# CPU_STM32F4.net
KiCad netlist of a schematic drawn in Altium Designer
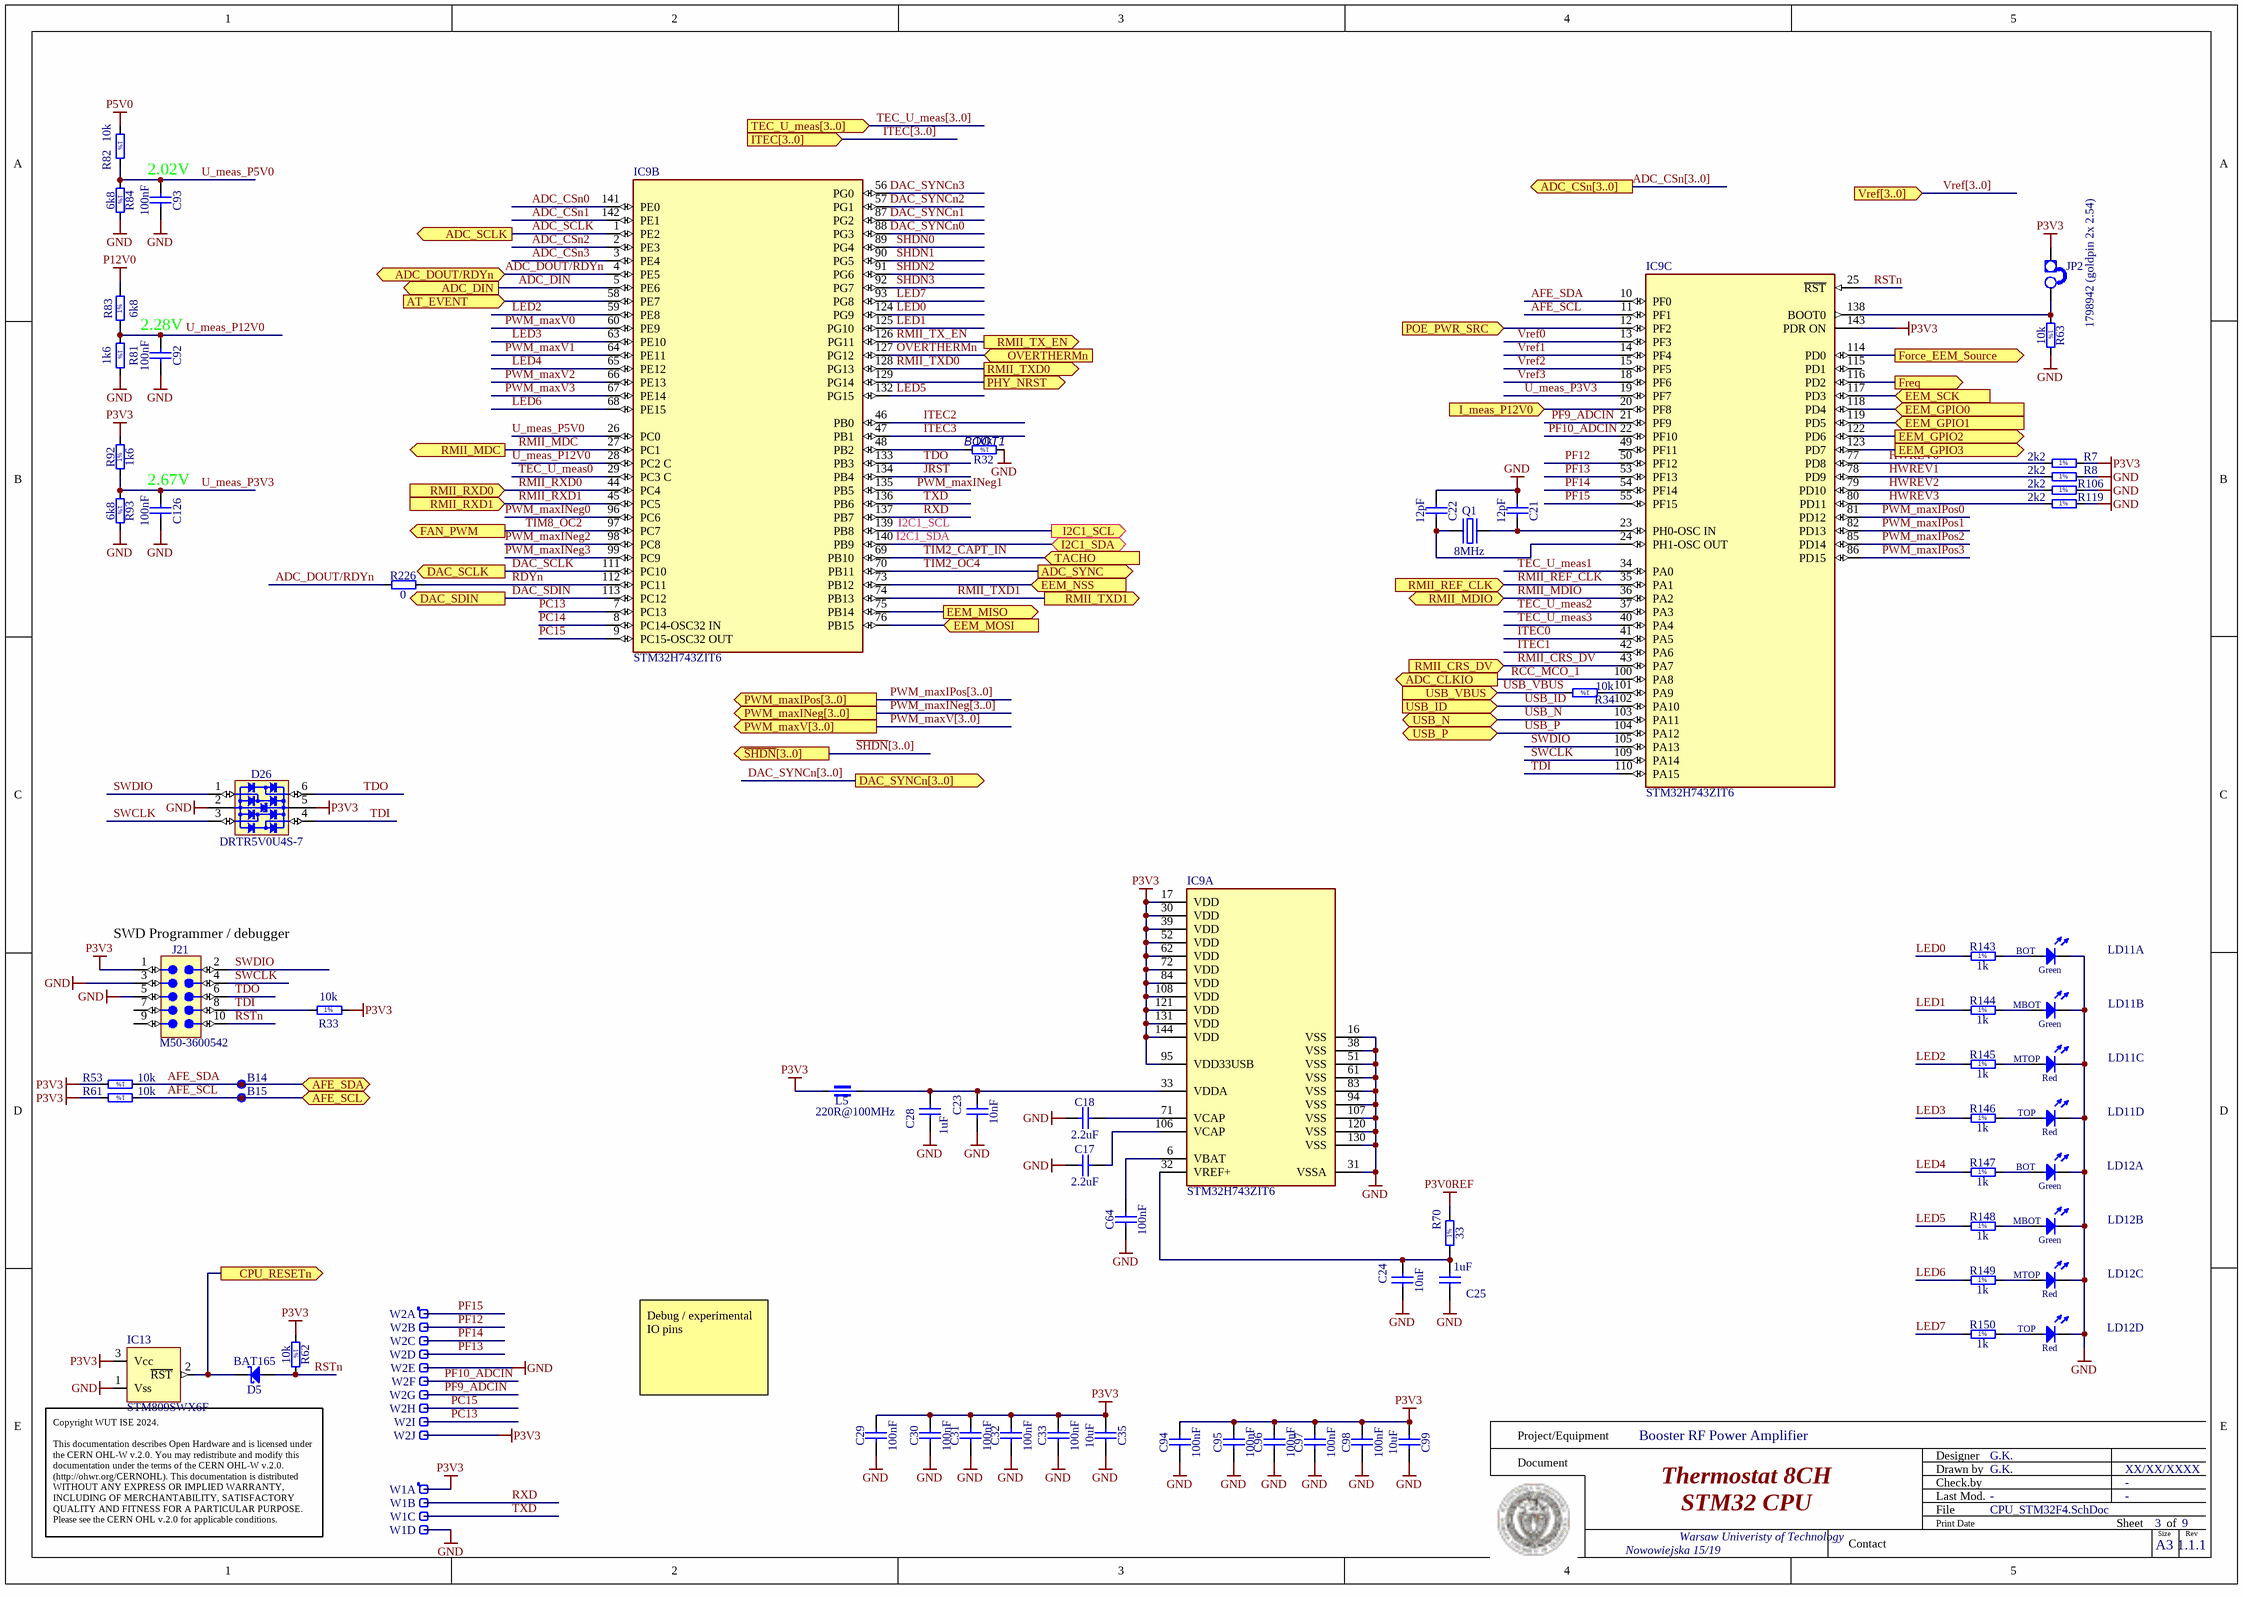
[diagram p0: CPU_STM32F4.SchDoc]

(export (version "E")
  (design (tool "Eeschema 10.0.6"))
  (components
    (comp (ref "B14")
      (value "SMD Pad")
      (footprint "C100")
      (description "Through Hole Pad")
      (fields (field (name "PART NUMBER") "SMD_PAD_D1MM") (field (name "AUTHOR") "CERN DEM JLC"))
      (libsource (lib "Eletro-mechanical") (part "Single SMD Pad (Round)"))
    )
    (comp (ref "B15")
      (value "SMD Pad")
      (footprint "C100")
      (description "Through Hole Pad")
      (fields (field (name "PART NUMBER") "SMD_PAD_D1MM") (field (name "AUTHOR") "CERN DEM JLC"))
      (libsource (lib "Eletro-mechanical") (part "Single SMD Pad (Round)"))
    )
    (comp (ref "C17")
      (value "2.2uF")
      (footprint "CAPC1608X90N")
      (description "Non-polarised capacitor")
      (fields
        (field (name "PART NUMBER") "CC0603_2.2UF_10V_20%_X7R")
        (field (name "VOLTAGE") "10V")
        (field (name "AUTHOR") "CERN DEM JLC")
      )
      (libsource (lib "Capacitors") (part "Capacitor - non polarized"))
    )
    (comp (ref "C18")
      (value "2.2uF")
      (footprint "CAPC1608X90N")
      (description "Non-polarised capacitor")
      (fields
        (field (name "PART NUMBER") "CC0603_2.2UF_10V_20%_X7R")
        (field (name "VOLTAGE") "10V")
        (field (name "AUTHOR") "CERN DEM JLC")
      )
      (libsource (lib "Capacitors") (part "Capacitor - non polarized"))
    )
    (comp (ref "C21")
      (value "12pF")
      (footprint "CAPC1005X55N")
      (description "Non-polarised capacitor")
      (fields
        (field (name "PART NUMBER") "CC0402_12PF_50V_5%_C0G")
        (field (name "VOLTAGE") "50V")
        (field (name "AUTHOR") "CERN DEM JLC")
      )
      (libsource (lib "Capacitors") (part "Capacitor - non polarized"))
    )
    (comp (ref "C22")
      (value "12pF")
      (footprint "CAPC1005X55N")
      (description "Non-polarised capacitor")
      (fields
        (field (name "PART NUMBER") "CC0402_12PF_50V_5%_C0G")
        (field (name "VOLTAGE") "50V")
        (field (name "AUTHOR") "CERN DEM JLC")
      )
      (libsource (lib "Capacitors") (part "Capacitor - non polarized"))
    )
    (comp (ref "C23")
      (value "10nF")
      (footprint "CAPC1005X55N")
      (description "Non-polarised capacitor")
      (fields
        (field (name "PART NUMBER") "CC0402_10NF_25V_10%_X7R")
        (field (name "VOLTAGE") "25V")
        (field (name "AUTHOR") "CERN DEM JLC")
      )
      (libsource (lib "Capacitors") (part "Capacitor - non polarized"))
    )
    (comp (ref "C24")
      (value "10nF")
      (footprint "CAPC1005X55N")
      (description "Non-polarised capacitor")
      (fields
        (field (name "PART NUMBER") "CC0402_10NF_25V_10%_X7R")
        (field (name "VOLTAGE") "25V")
        (field (name "AUTHOR") "CERN DEM JLC")
      )
      (libsource (lib "Capacitors") (part "Capacitor - non polarized"))
    )
    (comp (ref "C25")
      (value "1uF")
      (footprint "CAPC1608X87N")
      (description "Non-polarised capacitor")
      (fields
        (field (name "PART NUMBER") "CC0603_1UF_25V_10%_X7R")
        (field (name "VOLTAGE") "25V")
        (field (name "AUTHOR") "CERN DEM JLC")
      )
      (libsource (lib "Capacitors") (part "Capacitor - non polarized"))
    )
    (comp (ref "C28")
      (value "1uF")
      (footprint "CAPC1608X87N")
      (description "Non-polarised capacitor")
      (fields
        (field (name "PART NUMBER") "CC0603_1UF_25V_10%_X7R")
        (field (name "VOLTAGE") "25V")
        (field (name "AUTHOR") "CERN DEM JLC")
      )
      (libsource (lib "Capacitors") (part "Capacitor - non polarized"))
    )
    (comp (ref "C29")
      (value "100nF")
      (footprint "CAPC1005X55N")
      (description "Non-polarised capacitor")
      (fields
        (field (name "PART NUMBER") "CC0402_100NF_16V_10%_X5R")
        (field (name "VOLTAGE") "16V")
        (field (name "AUTHOR") "CERN DEM JLC")
      )
      (libsource (lib "Capacitors") (part "Capacitor - non polarized"))
    )
    (comp (ref "C30")
      (value "100nF")
      (footprint "CAPC1005X55N")
      (description "Non-polarised capacitor")
      (fields
        (field (name "PART NUMBER") "CC0402_100NF_16V_10%_X5R")
        (field (name "VOLTAGE") "16V")
        (field (name "AUTHOR") "CERN DEM JLC")
      )
      (libsource (lib "Capacitors") (part "Capacitor - non polarized"))
    )
    (comp (ref "C31")
      (value "100nF")
      (footprint "CAPC1005X55N")
      (description "Non-polarised capacitor")
      (fields
        (field (name "PART NUMBER") "CC0402_100NF_16V_10%_X5R")
        (field (name "VOLTAGE") "16V")
        (field (name "AUTHOR") "CERN DEM JLC")
      )
      (libsource (lib "Capacitors") (part "Capacitor - non polarized"))
    )
    (comp (ref "C32")
      (value "100nF")
      (footprint "CAPC1005X55N")
      (description "Non-polarised capacitor")
      (fields
        (field (name "PART NUMBER") "CC0402_100NF_16V_10%_X5R")
        (field (name "VOLTAGE") "16V")
        (field (name "AUTHOR") "CERN DEM JLC")
      )
      (libsource (lib "Capacitors") (part "Capacitor - non polarized"))
    )
    (comp (ref "C33")
      (value "100nF")
      (footprint "CAPC1005X55N")
      (description "Non-polarised capacitor")
      (fields
        (field (name "PART NUMBER") "CC0402_100NF_16V_10%_X5R")
        (field (name "VOLTAGE") "16V")
        (field (name "AUTHOR") "CERN DEM JLC")
      )
      (libsource (lib "Capacitors") (part "Capacitor - non polarized"))
    )
    (comp (ref "C35")
      (value "10uF")
      (footprint "CAPC2012X135N")
      (description "Non-polarised capacitor")
      (fields
        (field (name "PART NUMBER") "CC0805_10UF_16V_10%_X5R")
        (field (name "VOLTAGE") "16V")
        (field (name "AUTHOR") "CERN DEM JLC")
      )
      (libsource (lib "Capacitors") (part "Capacitor - non polarized"))
    )
    (comp (ref "C64")
      (value "100nF")
      (footprint "CAPC1005X55N")
      (description "Non-polarised capacitor")
      (fields
        (field (name "PART NUMBER") "CC0402_100NF_16V_10%_X5R")
        (field (name "VOLTAGE") "16V")
        (field (name "AUTHOR") "CERN DEM JLC")
      )
      (libsource (lib "Capacitors") (part "Capacitor - non polarized"))
    )
    (comp (ref "C92")
      (value "100nF")
      (footprint "CAPC1005X55N")
      (description "Non-polarised capacitor")
      (fields
        (field (name "PART NUMBER") "CC0402_100NF_16V_10%_X5R")
        (field (name "VOLTAGE") "16V")
        (field (name "AUTHOR") "CERN DEM JLC")
      )
      (libsource (lib "Capacitors") (part "Capacitor - non polarized"))
    )
    (comp (ref "C93")
      (value "100nF")
      (footprint "CAPC1005X55N")
      (description "Non-polarised capacitor")
      (fields
        (field (name "PART NUMBER") "CC0402_100NF_16V_10%_X5R")
        (field (name "VOLTAGE") "16V")
        (field (name "AUTHOR") "CERN DEM JLC")
      )
      (libsource (lib "Capacitors") (part "Capacitor - non polarized"))
    )
    (comp (ref "C94")
      (value "100nF")
      (footprint "CAPC1005X55N")
      (description "Non-polarised capacitor")
      (fields
        (field (name "PART NUMBER") "CC0402_100NF_16V_10%_X5R")
        (field (name "VOLTAGE") "16V")
        (field (name "AUTHOR") "CERN DEM JLC")
      )
      (libsource (lib "Capacitors") (part "Capacitor - non polarized"))
    )
    (comp (ref "C95")
      (value "100nF")
      (footprint "CAPC1005X55N")
      (description "Non-polarised capacitor")
      (fields
        (field (name "PART NUMBER") "CC0402_100NF_16V_10%_X5R")
        (field (name "VOLTAGE") "16V")
        (field (name "AUTHOR") "CERN DEM JLC")
      )
      (libsource (lib "Capacitors") (part "Capacitor - non polarized"))
    )
    (comp (ref "C96")
      (value "100nF")
      (footprint "CAPC1005X55N")
      (description "Non-polarised capacitor")
      (fields
        (field (name "PART NUMBER") "CC0402_100NF_16V_10%_X5R")
        (field (name "VOLTAGE") "16V")
        (field (name "AUTHOR") "CERN DEM JLC")
      )
      (libsource (lib "Capacitors") (part "Capacitor - non polarized"))
    )
    (comp (ref "C97")
      (value "100nF")
      (footprint "CAPC1005X55N")
      (description "Non-polarised capacitor")
      (fields
        (field (name "PART NUMBER") "CC0402_100NF_16V_10%_X5R")
        (field (name "VOLTAGE") "16V")
        (field (name "AUTHOR") "CERN DEM JLC")
      )
      (libsource (lib "Capacitors") (part "Capacitor - non polarized"))
    )
    (comp (ref "C98")
      (value "100nF")
      (footprint "CAPC1005X55N")
      (description "Non-polarised capacitor")
      (fields
        (field (name "PART NUMBER") "CC0402_100NF_16V_10%_X5R")
        (field (name "VOLTAGE") "16V")
        (field (name "AUTHOR") "CERN DEM JLC")
      )
      (libsource (lib "Capacitors") (part "Capacitor - non polarized"))
    )
    (comp (ref "C99")
      (value "10uF")
      (footprint "CAPC2012X135N")
      (description "Non-polarised capacitor")
      (fields
        (field (name "PART NUMBER") "CC0805_10UF_16V_10%_X5R")
        (field (name "VOLTAGE") "16V")
        (field (name "AUTHOR") "CERN DEM JLC")
      )
      (libsource (lib "Capacitors") (part "Capacitor - non polarized"))
    )
    (comp (ref "C126")
      (value "100nF")
      (footprint "CAPC1005X55N")
      (description "Non-polarised capacitor")
      (fields
        (field (name "PART NUMBER") "CC0402_100NF_16V_10%_X5R")
        (field (name "VOLTAGE") "16V")
        (field (name "AUTHOR") "CERN DEM JLC")
      )
      (libsource (lib "Capacitors") (part "Capacitor - non polarized"))
    )
    (comp (ref "D5")
      (value "BAT165")
      (footprint "SOD2512X110N")
      (description "Schottky Diode")
      (fields
        (field (name "VOLTAGE") "40V")
        (field (name "POWER") "750mA")
        (field (name "AUTHOR") "CERN DEM JLC")
      )
      (libsource (lib "ICs And Semiconductors") (part "Diode Schottky"))
    )
    (comp (ref "D26")
      (value "DRTR5V0U4S-7")
      (footprint "SOT65P210X110-6N")
      (description "Integrated Quad Ultra-Low Capacitance ESD Protection")
      (fields (field (name "MANUFACTURER") "DIODES") (field (name "AUTHOR") "GK"))
      (libsource (lib "Diodes") (part "D_TVS_DRTR5V0U4S-7"))
    )
    (comp (ref "IC9")
      (value "STM32H743ZIT6")
      (footprint "FP-LQFP144-1A-MFG")
      (description "IC MCU 32BIT 2MB FLASH 144LQFP")
      (fields
        (field (name "MANUFACTURER") "STMicroelectronics")
        (field (name "OCTOPART") "https://octopart.com/stm32h743zit6-stmicroelectronics-76372529")
      )
      (libsource (lib "Altium Content Vault") (part "4977c5c7f8d170b58ef15f889e64ba1"))
    )
    (comp (ref "IC13")
      (value "STM809SWX6F")
      (footprint "SOT-23")
      (description "2.93V  Reset circuit")
      (libsource (lib "LIBRARY_SCH") (part "VMON_STM809"))
    )
    (comp (ref "J21")
      (value "Header 10")
      (footprint "HARWIN_M50-3600542")
      (description "10 Contacts - Pitch 1.27mm - Dual Row SMT Vertical Pin Header (Post Lead = 3mm, Insulator 1mm)")
      (fields
        (field (name "PART NUMBER") "HARWIN_M50-3600542")
        (field (name "MANUFACTURER") "HARWIN")
        (field (name "MANUFACTURER PART NUMBER") "M50-3600542")
        (field (name "AUTHOR") "GK")
      )
      (libsource (lib "Connectors") (part "CON_2x10 1.27 SMT_male_HARWIN"))
    )
    (comp (ref "JP2")
      (value "1798942 (goldpin 2x 2.54)")
      (footprint "jump")
      (description "Jumper")
      (fields (field (name "MANUFACTURER PART NUMBER") "68001-102HLF"))
      (libsource (lib "LIBRARY_SCH") (part "JUMPER"))
    )
    (comp (ref "L5")
      (value "220R@100MHz")
      (footprint "INDC1005X55N")
      (fields
        (field (name "PART NUMBER") "IND0402_MURATA_BLM15HB221SN1")
        (field (name "POWER") "250mA")
        (field (name "TOLERANCE") "±25%")
        (field (name "AUTHOR") "CERN DEM JLC")
      )
      (libsource (lib "Inductors & Transformers") (part "Ferrite Bead"))
    )
    (comp (ref "LD11")
      (value "Green/Green/HeRed/HeRed")
      (footprint "LED_BIVAR_H485CHHGGDL")
      (description "LED x4 G-1C2A-BOT_G-3C4A_H-5C6A_H-7C8A-TOP")
      (fields
        (field (name "PART NUMBER") "LED_BIVAR_H485CHHGGDL")
        (field (name "MANUFACTURER") "BIVAR")
        (field (name "AUTHOR") "CERN DEM BC")
      )
      (libsource (lib "ICs And Semiconductors") (part "LED x4 G-1C2A-BOT_G-3C4A_H-5C6A_H-7C8A-TOP"))
    )
    (comp (ref "LD12")
      (value "Green/Green/HeRed/HeRed")
      (footprint "LED_BIVAR_H485CHHGGDL")
      (description "LED x4 G-1C2A-BOT_G-3C4A_H-5C6A_H-7C8A-TOP")
      (fields
        (field (name "PART NUMBER") "LED_BIVAR_H485CHHGGDL")
        (field (name "MANUFACTURER") "BIVAR")
        (field (name "AUTHOR") "CERN DEM BC")
      )
      (libsource (lib "ICs And Semiconductors") (part "LED x4 G-1C2A-BOT_G-3C4A_H-5C6A_H-7C8A-TOP"))
    )
    (comp (ref "Q1")
      (value "8MHz")
      (footprint "XTAL_TXC_7A")
      (description "Quartz Crystal")
      (fields
        (field (name "PART NUMBER") "XTAL_8MHZ_TXC_7A-8.000MAAE-T")
        (field (name "MANUFACTURER") "TXC CORPORATION")
        (field (name "AUTHOR") "CERN DEM JLC")
      )
      (libsource (lib "ICs And Semiconductors") (part "Quartz Crystal"))
    )
    (comp (ref "R7")
      (value "2k2")
      (footprint "RESC1005X40N")
      (description "Resistor - 1%")
      (fields
        (field (name "PART NUMBER") "R0402_2K2_1%_0.0625W_100PPM")
        (field (name "POWER") "0.0625W")
        (field (name "AUTHOR") "CERN DEM JLC")
      )
      (libsource (lib "Resistors") (part "Resistor - 1%"))
    )
    (comp (ref "R8")
      (value "2k2")
      (footprint "RESC1005X40N")
      (description "Resistor - 1%")
      (fields
        (field (name "PART NUMBER") "R0402_2K2_1%_0.0625W_100PPM")
        (field (name "POWER") "0.0625W")
        (field (name "AUTHOR") "CERN DEM JLC")
      )
      (libsource (lib "Resistors") (part "Resistor - 1%"))
    )
    (comp (ref "R32")
      (value "10k")
      (footprint "RESC1005X40N")
      (description "Resistor - 1%")
      (fields
        (field (name "PART NUMBER") "R0402_10K_1%_0.0625W_100PPM")
        (field (name "POWER") "0.0625W")
        (field (name "AUTHOR") "CERN DEM JLC")
      )
      (libsource (lib "Resistors") (part "Resistor - 1%"))
    )
    (comp (ref "R33")
      (value "10k")
      (footprint "RESC1005X40N")
      (description "Resistor - 1%")
      (fields
        (field (name "PART NUMBER") "R0402_10K_1%_0.0625W_100PPM")
        (field (name "POWER") "0.0625W")
        (field (name "AUTHOR") "CERN DEM JLC")
      )
      (libsource (lib "Resistors") (part "Resistor - 1%"))
    )
    (comp (ref "R34")
      (value "10k")
      (footprint "RESC1005X40N")
      (description "Resistor - 1%")
      (fields
        (field (name "PART NUMBER") "R0402_10K_1%_0.0625W_100PPM")
        (field (name "POWER") "0.0625W")
        (field (name "AUTHOR") "CERN DEM JLC")
      )
      (libsource (lib "Resistors") (part "Resistor - 1%"))
    )
    (comp (ref "R53")
      (value "10k")
      (footprint "RESC1005X40N")
      (description "Resistor - 1%")
      (fields
        (field (name "PART NUMBER") "R0402_10K_1%_0.0625W_100PPM")
        (field (name "POWER") "0.0625W")
        (field (name "AUTHOR") "CERN DEM JLC")
      )
      (libsource (lib "Resistors") (part "Resistor - 1%"))
    )
    (comp (ref "R61")
      (value "10k")
      (footprint "RESC1005X40N")
      (description "Resistor - 1%")
      (fields
        (field (name "PART NUMBER") "R0402_10K_1%_0.0625W_100PPM")
        (field (name "POWER") "0.0625W")
        (field (name "AUTHOR") "CERN DEM JLC")
      )
      (libsource (lib "Resistors") (part "Resistor - 1%"))
    )
    (comp (ref "R62")
      (value "10k")
      (footprint "RESC1005X40N")
      (description "Resistor - 1%")
      (fields
        (field (name "PART NUMBER") "R0402_10K_1%_0.0625W_100PPM")
        (field (name "POWER") "0.0625W")
        (field (name "AUTHOR") "CERN DEM JLC")
      )
      (libsource (lib "Resistors") (part "Resistor - 1%"))
    )
    (comp (ref "R63")
      (value "10k")
      (footprint "RESC1005X40N")
      (description "Resistor - 1%")
      (fields
        (field (name "PART NUMBER") "R0402_10K_1%_0.0625W_100PPM")
        (field (name "POWER") "0.0625W")
        (field (name "AUTHOR") "CERN DEM JLC")
      )
      (libsource (lib "Resistors") (part "Resistor - 1%"))
    )
    (comp (ref "R70")
      (value "33")
      (footprint "RESC1005X40N")
      (description "Resistor - 1%")
      (fields
        (field (name "PART NUMBER") "R0402_33R_1%_0.0625W_100PPM")
        (field (name "POWER") "0.0625W")
        (field (name "AUTHOR") "CERN DEM JLC")
      )
      (libsource (lib "Resistors") (part "Resistor - 1%"))
    )
    (comp (ref "R81")
      (value "1k6")
      (footprint "RESC1005X40N")
      (description "Resistor - 1%")
      (fields
        (field (name "PART NUMBER") "R0402_1K6_1%_0.0625W_100PPM")
        (field (name "POWER") "0.0625W")
        (field (name "AUTHOR") "CERN DEM JLC")
      )
      (libsource (lib "Resistors") (part "Resistor - 1%"))
    )
    (comp (ref "R82")
      (value "10k")
      (footprint "RESC1005X40N")
      (description "Resistor - 1%")
      (fields
        (field (name "PART NUMBER") "R0402_10K_1%_0.0625W_100PPM")
        (field (name "POWER") "0.0625W")
        (field (name "AUTHOR") "CERN DEM JLC")
      )
      (libsource (lib "Resistors") (part "Resistor - 1%"))
    )
    (comp (ref "R83")
      (value "6k8")
      (footprint "RESC1005X40N")
      (description "Resistor - 1%")
      (fields
        (field (name "PART NUMBER") "R0402_6K8_1%_0.0625W_100PPM")
        (field (name "POWER") "0.0625W")
        (field (name "AUTHOR") "CERN DEM JLC")
      )
      (libsource (lib "Resistors") (part "Resistor - 1%"))
    )
    (comp (ref "R84")
      (value "6k8")
      (footprint "RESC1005X40N")
      (description "Resistor - 1%")
      (fields
        (field (name "PART NUMBER") "R0402_6K8_1%_0.0625W_100PPM")
        (field (name "POWER") "0.0625W")
        (field (name "AUTHOR") "CERN DEM JLC")
      )
      (libsource (lib "Resistors") (part "Resistor - 1%"))
    )
    (comp (ref "R92")
      (value "1k6")
      (footprint "RESC1005X40N")
      (description "Resistor - 1%")
      (fields
        (field (name "PART NUMBER") "R0402_1K6_1%_0.0625W_100PPM")
        (field (name "POWER") "0.0625W")
        (field (name "AUTHOR") "CERN DEM JLC")
      )
      (libsource (lib "Resistors") (part "Resistor - 1%"))
    )
    (comp (ref "R93")
      (value "6k8")
      (footprint "RESC1005X40N")
      (description "Resistor - 1%")
      (fields
        (field (name "PART NUMBER") "R0402_6K8_1%_0.0625W_100PPM")
        (field (name "POWER") "0.0625W")
        (field (name "AUTHOR") "CERN DEM JLC")
      )
      (libsource (lib "Resistors") (part "Resistor - 1%"))
    )
    (comp (ref "R106")
      (value "2k2")
      (footprint "RESC1005X40N")
      (description "Resistor - 1%")
      (fields
        (field (name "PART NUMBER") "R0402_2K2_1%_0.0625W_100PPM")
        (field (name "POWER") "0.0625W")
        (field (name "AUTHOR") "CERN DEM JLC")
      )
      (libsource (lib "Resistors") (part "Resistor - 1%"))
    )
    (comp (ref "R119")
      (value "2k2")
      (footprint "RESC1005X40N")
      (description "Resistor - 1%")
      (fields
        (field (name "PART NUMBER") "R0402_2K2_1%_0.0625W_100PPM")
        (field (name "POWER") "0.0625W")
        (field (name "AUTHOR") "CERN DEM JLC")
      )
      (libsource (lib "Resistors") (part "Resistor - 1%"))
    )
    (comp (ref "R143")
      (value "1k")
      (footprint "RESC1005X40N")
      (description "Resistor - 1%")
      (fields
        (field (name "PART NUMBER") "R0402_1K_1%_0.0625W_100PPM")
        (field (name "POWER") "0.0625W")
        (field (name "AUTHOR") "CERN DEM JLC")
      )
      (libsource (lib "Resistors") (part "Resistor - 1%"))
    )
    (comp (ref "R144")
      (value "1k")
      (footprint "RESC1005X40N")
      (description "Resistor - 1%")
      (fields
        (field (name "PART NUMBER") "R0402_1K_1%_0.0625W_100PPM")
        (field (name "POWER") "0.0625W")
        (field (name "AUTHOR") "CERN DEM JLC")
      )
      (libsource (lib "Resistors") (part "Resistor - 1%"))
    )
    (comp (ref "R145")
      (value "1k")
      (footprint "RESC1005X40N")
      (description "Resistor - 1%")
      (fields
        (field (name "PART NUMBER") "R0402_1K_1%_0.0625W_100PPM")
        (field (name "POWER") "0.0625W")
        (field (name "AUTHOR") "CERN DEM JLC")
      )
      (libsource (lib "Resistors") (part "Resistor - 1%"))
    )
    (comp (ref "R146")
      (value "1k")
      (footprint "RESC1005X40N")
      (description "Resistor - 1%")
      (fields
        (field (name "PART NUMBER") "R0402_1K_1%_0.0625W_100PPM")
        (field (name "POWER") "0.0625W")
        (field (name "AUTHOR") "CERN DEM JLC")
      )
      (libsource (lib "Resistors") (part "Resistor - 1%"))
    )
    (comp (ref "R147")
      (value "1k")
      (footprint "RESC1005X40N")
      (description "Resistor - 1%")
      (fields
        (field (name "PART NUMBER") "R0402_1K_1%_0.0625W_100PPM")
        (field (name "POWER") "0.0625W")
        (field (name "AUTHOR") "CERN DEM JLC")
      )
      (libsource (lib "Resistors") (part "Resistor - 1%"))
    )
    (comp (ref "R148")
      (value "1k")
      (footprint "RESC1005X40N")
      (description "Resistor - 1%")
      (fields
        (field (name "PART NUMBER") "R0402_1K_1%_0.0625W_100PPM")
        (field (name "POWER") "0.0625W")
        (field (name "AUTHOR") "CERN DEM JLC")
      )
      (libsource (lib "Resistors") (part "Resistor - 1%"))
    )
    (comp (ref "R149")
      (value "1k")
      (footprint "RESC1005X40N")
      (description "Resistor - 1%")
      (fields
        (field (name "PART NUMBER") "R0402_1K_1%_0.0625W_100PPM")
        (field (name "POWER") "0.0625W")
        (field (name "AUTHOR") "CERN DEM JLC")
      )
      (libsource (lib "Resistors") (part "Resistor - 1%"))
    )
    (comp (ref "R150")
      (value "1k")
      (footprint "RESC1005X40N")
      (description "Resistor - 1%")
      (fields
        (field (name "PART NUMBER") "R0402_1K_1%_0.0625W_100PPM")
        (field (name "POWER") "0.0625W")
        (field (name "AUTHOR") "CERN DEM JLC")
      )
      (libsource (lib "Resistors") (part "Resistor - 1%"))
    )
    (comp (ref "R226")
      (value "0")
      (footprint "RESC1005X40N")
      (description "Resistor")
      (fields
        (field (name "PART NUMBER") "R0402_0R_JUMPER")
        (field (name "MANUFACTURER") "GENERIC")
        (field (name "AUTHOR") "CERN DEM JLC")
      )
      (libsource (lib "Resistors") (part "Resistor"))
    )
    (comp (ref "W1")
      (value "Header 4")
      (footprint "SAMTEC_HTSW-104-23-L-S")
      (description "4 Mini Wire-Wrap Contact Strip Header")
      (fields
        (field (name "PART NUMBER") "SAMTEC_HTSW-104-23-L-S")
        (field (name "MANUFACTURER") "SAMTEC")
        (field (name "AUTHOR") "CERN DEM JLC")
      )
      (libsource (lib "Connectors") (part "Wire-Wrap Contact x4"))
    )
    (comp (ref "W2")
      (value "Header 10")
      (footprint "SAMTEC_MTLW-110-07-L-S-250")
      (description "10 Mini Wire-Wrap Contact Strip Header")
      (fields
        (field (name "PART NUMBER") "SAMTEC_MTLW-110-07-L-S-250")
        (field (name "MANUFACTURER") "SAMTEC")
        (field (name "AUTHOR") "CERN DEM JLC")
      )
      (libsource (lib "Connectors") (part "Wire-Wrap Contact x10"))
    )
  )
  (nets
    (net (code "1") (name "/ADC_CSn0") (class "Default")
      (node (ref "IC9") (pin "141") (pinfunction "PE0_141") (pintype "bidirectional"))
    )
    (net (code "2") (name "/ADC_CSn1") (class "Default")
      (node (ref "IC9") (pin "142") (pinfunction "PE1_142") (pintype "bidirectional"))
    )
    (net (code "3") (name "/ADC_CSn2") (class "Default")
      (node (ref "IC9") (pin "2") (pinfunction "PE3_2") (pintype "bidirectional"))
    )
    (net (code "4") (name "/ADC_CSn3") (class "Default")
      (node (ref "IC9") (pin "3") (pinfunction "PE4_3") (pintype "bidirectional"))
    )
    (net (code "6") (name "/ADC_DIN") (class "Default")
      (node (ref "IC9") (pin "5") (pinfunction "PE6_5") (pintype "bidirectional"))
    )
    (net (code "7") (name "/ADC_DOUT{slash}RDYn") (class "Default")
      (node (ref "IC9") (pin "4") (pinfunction "PE5_4") (pintype "bidirectional"))
      (node (ref "R226") (pin "1") (pinfunction "1_1") (pintype "passive"))
    )
    (net (code "8") (name "/ADC_SCLK") (class "Default")
      (node (ref "IC9") (pin "1") (pinfunction "PE2_1") (pintype "bidirectional"))
    )
    (net (code "9") (name "/AFE_SCL") (class "Default")
      (node (ref "B15") (pin "1") (pinfunction "1_1") (pintype "bidirectional"))
      (node (ref "IC9") (pin "11") (pinfunction "PF1_11") (pintype "bidirectional"))
      (node (ref "R61") (pin "1") (pinfunction "1_1") (pintype "passive"))
    )
    (net (code "10") (name "/AFE_SDA") (class "Default")
      (node (ref "B14") (pin "1") (pinfunction "1_1") (pintype "bidirectional"))
      (node (ref "IC9") (pin "10") (pinfunction "PF0_10") (pintype "bidirectional"))
      (node (ref "R53") (pin "1") (pinfunction "1_1") (pintype "passive"))
    )
    (net (code "11") (name "/AT_EVENT") (class "Default")
      (node (ref "IC9") (pin "58") (pinfunction "PE7_58") (pintype "bidirectional"))
    )
    (net (code "12") (name "/CPU_RESETn") (class "Default")
      (node (ref "D5") (pin "1") (pinfunction "C_1") (pintype "passive"))
      (node (ref "IC13") (pin "2") (pinfunction "~{RST}_2") (pintype "output"))
    )
    (net (code "13") (name "/DAC_SCLK") (class "Default")
      (node (ref "IC9") (pin "111") (pinfunction "PC10_111") (pintype "bidirectional"))
    )
    (net (code "14") (name "/DAC_SDIN") (class "Default")
      (node (ref "IC9") (pin "113") (pinfunction "PC12_113") (pintype "bidirectional"))
    )
    (net (code "15") (name "/DAC_SYNCn0") (class "Default")
      (node (ref "IC9") (pin "88") (pinfunction "PG3_88") (pintype "bidirectional"))
    )
    (net (code "16") (name "/DAC_SYNCn1") (class "Default")
      (node (ref "IC9") (pin "87") (pinfunction "PG2_87") (pintype "bidirectional"))
    )
    (net (code "17") (name "/DAC_SYNCn2") (class "Default")
      (node (ref "IC9") (pin "57") (pinfunction "PG1_57") (pintype "bidirectional"))
    )
    (net (code "18") (name "/DAC_SYNCn3") (class "Default")
      (node (ref "IC9") (pin "56") (pinfunction "PG0_56") (pintype "bidirectional"))
    )
    (net (code "20") (name "/EEM_GPIO0") (class "Default")
      (node (ref "IC9") (pin "118") (pinfunction "PD4_118") (pintype "bidirectional"))
    )
    (net (code "21") (name "/EEM_GPIO1") (class "Default")
      (node (ref "IC9") (pin "119") (pinfunction "PD5_119") (pintype "bidirectional"))
    )
    (net (code "22") (name "/EEM_GPIO2") (class "Default")
      (node (ref "IC9") (pin "122") (pinfunction "PD6_122") (pintype "bidirectional"))
    )
    (net (code "23") (name "/EEM_GPIO3") (class "Default")
      (node (ref "IC9") (pin "123") (pinfunction "PD7_123") (pintype "bidirectional"))
    )
    (net (code "24") (name "/EEM_MISO") (class "Default")
      (node (ref "IC9") (pin "75") (pinfunction "PB14_75") (pintype "bidirectional"))
    )
    (net (code "25") (name "/EEM_MOSI") (class "Default")
      (node (ref "IC9") (pin "76") (pinfunction "PB15_76") (pintype "bidirectional"))
    )
    (net (code "26") (name "/EEM_NSS") (class "Default")
      (node (ref "IC9") (pin "73") (pinfunction "PB12_73") (pintype "bidirectional"))
    )
    (net (code "27") (name "/EEM_SCK") (class "Default")
      (node (ref "IC9") (pin "117") (pinfunction "PD3_117") (pintype "bidirectional"))
    )
    (net (code "28") (name "/Force_EEM_Source") (class "Default")
      (node (ref "IC9") (pin "114") (pinfunction "PD0_114") (pintype "bidirectional"))
    )
    (net (code "29") (name "/Freq") (class "Default")
      (node (ref "IC9") (pin "116") (pinfunction "PD2_116") (pintype "bidirectional"))
    )
    (net (code "30") (name "/HWREV0") (class "Default")
      (node (ref "IC9") (pin "77") (pinfunction "PD8_77") (pintype "bidirectional"))
      (node (ref "R7") (pin "1") (pinfunction "1_1") (pintype "passive"))
    )
    (net (code "31") (name "/HWREV1") (class "Default")
      (node (ref "IC9") (pin "78") (pinfunction "PD9_78") (pintype "bidirectional"))
      (node (ref "R8") (pin "1") (pinfunction "1_1") (pintype "passive"))
    )
    (net (code "32") (name "/HWREV2") (class "Default")
      (node (ref "IC9") (pin "79") (pinfunction "PD10_79") (pintype "bidirectional"))
      (node (ref "R106") (pin "1") (pinfunction "1_1") (pintype "passive"))
    )
    (net (code "33") (name "/HWREV3") (class "Default")
      (node (ref "IC9") (pin "80") (pinfunction "PD11_80") (pintype "bidirectional"))
      (node (ref "R119") (pin "1") (pinfunction "1_1") (pintype "passive"))
    )
    (net (code "34") (name "/I2C1_SCL") (class "Default")
      (node (ref "IC9") (pin "139") (pinfunction "PB8_139") (pintype "bidirectional"))
    )
    (net (code "35") (name "/I2C1_SDA") (class "Default")
      (node (ref "IC9") (pin "140") (pinfunction "PB9_140") (pintype "bidirectional"))
    )
    (net (code "36") (name "/ITEC0") (class "Default")
      (node (ref "IC9") (pin "41") (pinfunction "PA5_41") (pintype "bidirectional"))
    )
    (net (code "37") (name "/ITEC1") (class "Default")
      (node (ref "IC9") (pin "42") (pinfunction "PA6_42") (pintype "bidirectional"))
    )
    (net (code "38") (name "/ITEC2") (class "Default")
      (node (ref "IC9") (pin "46") (pinfunction "PB0_46") (pintype "bidirectional"))
    )
    (net (code "39") (name "/ITEC3") (class "Default")
      (node (ref "IC9") (pin "47") (pinfunction "PB1_47") (pintype "bidirectional"))
    )
    (net (code "41") (name "/I_meas_P12V0") (class "Default")
      (node (ref "IC9") (pin "20") (pinfunction "PF8_20") (pintype "bidirectional"))
    )
    (net (code "42") (name "/JRST") (class "Default")
      (node (ref "IC9") (pin "134") (pinfunction "PB4_134") (pintype "bidirectional"))
    )
    (net (code "43") (name "/LED0") (class "Default")
      (node (ref "IC9") (pin "124") (pinfunction "PG9_124") (pintype "bidirectional"))
      (node (ref "R143") (pin "1") (pinfunction "1_1") (pintype "passive"))
    )
    (net (code "44") (name "/LED1") (class "Default")
      (node (ref "IC9") (pin "125") (pinfunction "PG10_125") (pintype "bidirectional"))
      (node (ref "R144") (pin "1") (pinfunction "1_1") (pintype "passive"))
    )
    (net (code "45") (name "/LED2") (class "Default")
      (node (ref "IC9") (pin "59") (pinfunction "PE8_59") (pintype "bidirectional"))
      (node (ref "R145") (pin "1") (pinfunction "1_1") (pintype "passive"))
    )
    (net (code "46") (name "/LED3") (class "Default")
      (node (ref "IC9") (pin "63") (pinfunction "PE10_63") (pintype "bidirectional"))
      (node (ref "R146") (pin "1") (pinfunction "1_1") (pintype "passive"))
    )
    (net (code "47") (name "/LED4") (class "Default")
      (node (ref "IC9") (pin "65") (pinfunction "PE12_65") (pintype "bidirectional"))
      (node (ref "R147") (pin "1") (pinfunction "1_1") (pintype "passive"))
    )
    (net (code "48") (name "/LED5") (class "Default")
      (node (ref "IC9") (pin "132") (pinfunction "PG15_132") (pintype "bidirectional"))
      (node (ref "R148") (pin "1") (pinfunction "1_1") (pintype "passive"))
    )
    (net (code "49") (name "/LED6") (class "Default")
      (node (ref "IC9") (pin "68") (pinfunction "PE15_68") (pintype "bidirectional"))
      (node (ref "R149") (pin "1") (pinfunction "1_1") (pintype "passive"))
    )
    (net (code "50") (name "/LED7") (class "Default")
      (node (ref "IC9") (pin "93") (pinfunction "PG8_93") (pintype "bidirectional"))
      (node (ref "R150") (pin "1") (pinfunction "1_1") (pintype "passive"))
    )
    (net (code "51") (name "/OVERTHERMn") (class "Default")
      (node (ref "IC9") (pin "127") (pinfunction "PG12_127") (pintype "bidirectional"))
    )
    (net (code "52") (name "/PC13") (class "Default")
      (node (ref "IC9") (pin "7") (pinfunction "PC13_7") (pintype "bidirectional"))
      (node (ref "W2") (pin "9") (pinfunction "9_9") (pintype "bidirectional"))
    )
    (net (code "53") (name "/PC14") (class "Default")
      (node (ref "IC9") (pin "8") (pinfunction "PC14-OSC32_IN_8") (pintype "bidirectional"))
    )
    (net (code "54") (name "/PC15") (class "Default")
      (node (ref "IC9") (pin "9") (pinfunction "PC15-OSC32_OUT_9") (pintype "bidirectional"))
      (node (ref "W2") (pin "8") (pinfunction "8_8") (pintype "bidirectional"))
    )
    (net (code "55") (name "/PF9_ADCIN") (class "Default")
      (node (ref "IC9") (pin "21") (pinfunction "PF9_21") (pintype "bidirectional"))
      (node (ref "W2") (pin "7") (pinfunction "7_7") (pintype "bidirectional"))
    )
    (net (code "56") (name "/PF10_ADCIN") (class "Default")
      (node (ref "IC9") (pin "22") (pinfunction "PF10_22") (pintype "bidirectional"))
      (node (ref "W2") (pin "6") (pinfunction "6_6") (pintype "bidirectional"))
    )
    (net (code "57") (name "/PF12") (class "Default")
      (node (ref "IC9") (pin "50") (pinfunction "PF12_50") (pintype "bidirectional"))
      (node (ref "W2") (pin "2") (pinfunction "2_2") (pintype "bidirectional"))
    )
    (net (code "58") (name "/PF13") (class "Default")
      (node (ref "IC9") (pin "53") (pinfunction "PF13_53") (pintype "bidirectional"))
      (node (ref "W2") (pin "4") (pinfunction "4_4") (pintype "bidirectional"))
    )
    (net (code "59") (name "/PF14") (class "Default")
      (node (ref "IC9") (pin "54") (pinfunction "PF14_54") (pintype "bidirectional"))
      (node (ref "W2") (pin "3") (pinfunction "3_3") (pintype "bidirectional"))
    )
    (net (code "60") (name "/PF15") (class "Default")
      (node (ref "IC9") (pin "55") (pinfunction "PF15_55") (pintype "bidirectional"))
      (node (ref "W2") (pin "1") (pinfunction "1_1") (pintype "bidirectional"))
    )
    (net (code "61") (name "/PHY_NRST") (class "Default")
      (node (ref "IC9") (pin "129") (pinfunction "PG14_129") (pintype "bidirectional"))
    )
    (net (code "62") (name "/POE_PWR_SRC") (class "Default")
      (node (ref "IC9") (pin "12") (pinfunction "PF2_12") (pintype "bidirectional"))
    )
    (net (code "63") (name "/PWM_maxINeg0") (class "Default")
      (node (ref "IC9") (pin "96") (pinfunction "PC6_96") (pintype "bidirectional"))
    )
    (net (code "64") (name "/PWM_maxINeg1") (class "Default")
      (node (ref "IC9") (pin "135") (pinfunction "PB5_135") (pintype "bidirectional"))
    )
    (net (code "65") (name "/PWM_maxINeg2") (class "Default")
      (node (ref "IC9") (pin "98") (pinfunction "PC8_98") (pintype "bidirectional"))
    )
    (net (code "66") (name "/PWM_maxINeg3") (class "Default")
      (node (ref "IC9") (pin "99") (pinfunction "PC9_99") (pintype "bidirectional"))
    )
    (net (code "68") (name "/PWM_maxIPos0") (class "Default")
      (node (ref "IC9") (pin "81") (pinfunction "PD12_81") (pintype "bidirectional"))
    )
    (net (code "69") (name "/PWM_maxIPos1") (class "Default")
      (node (ref "IC9") (pin "82") (pinfunction "PD13_82") (pintype "bidirectional"))
    )
    (net (code "70") (name "/PWM_maxIPos2") (class "Default")
      (node (ref "IC9") (pin "85") (pinfunction "PD14_85") (pintype "bidirectional"))
    )
    (net (code "71") (name "/PWM_maxIPos3") (class "Default")
      (node (ref "IC9") (pin "86") (pinfunction "PD15_86") (pintype "bidirectional"))
    )
    (net (code "73") (name "/PWM_maxV0") (class "Default")
      (node (ref "IC9") (pin "60") (pinfunction "PE9_60") (pintype "bidirectional"))
    )
    (net (code "74") (name "/PWM_maxV1") (class "Default")
      (node (ref "IC9") (pin "64") (pinfunction "PE11_64") (pintype "bidirectional"))
    )
    (net (code "75") (name "/PWM_maxV2") (class "Default")
      (node (ref "IC9") (pin "66") (pinfunction "PE13_66") (pintype "bidirectional"))
    )
    (net (code "76") (name "/PWM_maxV3") (class "Default")
      (node (ref "IC9") (pin "67") (pinfunction "PE14_67") (pintype "bidirectional"))
    )
    (net (code "78") (name "/RCC_MCO_1") (class "Default")
      (node (ref "IC9") (pin "100") (pinfunction "PA8_100") (pintype "bidirectional"))
    )
    (net (code "79") (name "/RDYn") (class "Default")
      (node (ref "IC9") (pin "112") (pinfunction "PC11_112") (pintype "bidirectional"))
      (node (ref "R226") (pin "2") (pinfunction "2_2") (pintype "passive"))
    )
    (net (code "80") (name "/RMII_CRS_DV") (class "Default")
      (node (ref "IC9") (pin "43") (pinfunction "PA7_43") (pintype "bidirectional"))
    )
    (net (code "81") (name "/RMII_MDC") (class "Default")
      (node (ref "IC9") (pin "27") (pinfunction "PC1_27") (pintype "bidirectional"))
    )
    (net (code "82") (name "/RMII_MDIO") (class "Default")
      (node (ref "IC9") (pin "36") (pinfunction "PA2_36") (pintype "bidirectional"))
    )
    (net (code "83") (name "/RMII_REF_CLK") (class "Default")
      (node (ref "IC9") (pin "35") (pinfunction "PA1_35") (pintype "bidirectional"))
    )
    (net (code "84") (name "/RMII_RXD0") (class "Default")
      (node (ref "IC9") (pin "44") (pinfunction "PC4_44") (pintype "bidirectional"))
    )
    (net (code "85") (name "/RMII_RXD1") (class "Default")
      (node (ref "IC9") (pin "45") (pinfunction "PC5_45") (pintype "bidirectional"))
    )
    (net (code "86") (name "/RMII_TXD0") (class "Default")
      (node (ref "IC9") (pin "128") (pinfunction "PG13_128") (pintype "bidirectional"))
    )
    (net (code "87") (name "/RMII_TXD1") (class "Default")
      (node (ref "IC9") (pin "74") (pinfunction "PB13_74") (pintype "bidirectional"))
    )
    (net (code "88") (name "/RMII_TX_EN") (class "Default")
      (node (ref "IC9") (pin "126") (pinfunction "PG11_126") (pintype "bidirectional"))
    )
    (net (code "89") (name "/RSTn") (class "Default")
      (node (ref "D5") (pin "2") (pinfunction "A_2") (pintype "passive"))
      (node (ref "IC9") (pin "25") (pinfunction "~{RST}_25") (pintype "input"))
      (node (ref "J21") (pin "10") (pinfunction "10_10") (pintype "bidirectional"))
      (node (ref "R62") (pin "2") (pinfunction "2_2") (pintype "passive"))
    )
    (net (code "90") (name "/RXD") (class "Default")
      (node (ref "IC9") (pin "137") (pinfunction "PB7_137") (pintype "bidirectional"))
      (node (ref "W1") (pin "2") (pinfunction "2_2") (pintype "bidirectional"))
    )
    (net (code "91") (name "/SWCLK") (class "Default")
      (node (ref "D26") (pin "3") (pinfunction "I/O2_3") (pintype "bidirectional"))
      (node (ref "IC9") (pin "109") (pinfunction "PA14_109") (pintype "bidirectional"))
      (node (ref "J21") (pin "4") (pinfunction "4_4") (pintype "bidirectional"))
    )
    (net (code "92") (name "/SWDIO") (class "Default")
      (node (ref "D26") (pin "1") (pinfunction "I/O1_1") (pintype "bidirectional"))
      (node (ref "IC9") (pin "105") (pinfunction "PA13_105") (pintype "bidirectional"))
      (node (ref "J21") (pin "2") (pinfunction "2_2") (pintype "bidirectional"))
    )
    (net (code "93") (name "/TDI") (class "Default")
      (node (ref "D26") (pin "4") (pinfunction "I/O3_4") (pintype "bidirectional"))
      (node (ref "IC9") (pin "110") (pinfunction "PA15_110") (pintype "bidirectional"))
      (node (ref "J21") (pin "8") (pinfunction "8_8") (pintype "bidirectional"))
      (node (ref "R33") (pin "1") (pinfunction "1_1") (pintype "passive"))
    )
    (net (code "94") (name "/TDO") (class "Default")
      (node (ref "D26") (pin "6") (pinfunction "I/O4_6") (pintype "bidirectional"))
      (node (ref "IC9") (pin "133") (pinfunction "PB3_133") (pintype "bidirectional"))
      (node (ref "J21") (pin "6") (pinfunction "6_6") (pintype "bidirectional"))
    )
    (net (code "95") (name "/TEC_U_meas0") (class "Default")
      (node (ref "IC9") (pin "29") (pinfunction "PC3_C_29") (pintype "bidirectional"))
    )
    (net (code "96") (name "/TEC_U_meas1") (class "Default")
      (node (ref "IC9") (pin "34") (pinfunction "PA0_34") (pintype "bidirectional"))
    )
    (net (code "97") (name "/TEC_U_meas2") (class "Default")
      (node (ref "IC9") (pin "37") (pinfunction "PA3_37") (pintype "bidirectional"))
    )
    (net (code "98") (name "/TEC_U_meas3") (class "Default")
      (node (ref "IC9") (pin "40") (pinfunction "PA4_40") (pintype "bidirectional"))
    )
    (net (code "100") (name "/TIM2_CAPT_IN") (class "Default")
      (node (ref "IC9") (pin "69") (pinfunction "PB10_69") (pintype "bidirectional"))
    )
    (net (code "101") (name "/TIM2_OC4") (class "Default")
      (node (ref "IC9") (pin "70") (pinfunction "PB11_70") (pintype "bidirectional"))
    )
    (net (code "102") (name "/TIM8_OC2") (class "Default")
      (node (ref "IC9") (pin "97") (pinfunction "PC7_97") (pintype "bidirectional"))
    )
    (net (code "103") (name "/TXD") (class "Default")
      (node (ref "IC9") (pin "136") (pinfunction "PB6_136") (pintype "bidirectional"))
      (node (ref "W1") (pin "3") (pinfunction "3_3") (pintype "bidirectional"))
    )
    (net (code "104") (name "/USB_ID") (class "Default")
      (node (ref "IC9") (pin "102") (pinfunction "PA10_102") (pintype "bidirectional"))
    )
    (net (code "105") (name "/USB_N") (class "Default")
      (node (ref "IC9") (pin "103") (pinfunction "PA11_103") (pintype "bidirectional"))
    )
    (net (code "106") (name "/USB_P") (class "Default")
      (node (ref "IC9") (pin "104") (pinfunction "PA12_104") (pintype "bidirectional"))
    )
    (net (code "107") (name "/USB_VBUS") (class "Default")
      (node (ref "R34") (pin "2") (pinfunction "2_2") (pintype "passive"))
    )
    (net (code "108") (name "/U_meas_P3V3") (class "Default")
      (node (ref "C126") (pin "1") (pinfunction "1_1") (pintype "passive"))
      (node (ref "IC9") (pin "19") (pinfunction "PF7_19") (pintype "bidirectional"))
      (node (ref "R92") (pin "1") (pinfunction "1_1") (pintype "passive"))
      (node (ref "R93") (pin "1") (pinfunction "1_1") (pintype "passive"))
    )
    (net (code "109") (name "/U_meas_P5V0") (class "Default")
      (node (ref "C93") (pin "1") (pinfunction "1_1") (pintype "passive"))
      (node (ref "IC9") (pin "26") (pinfunction "PC0_26") (pintype "bidirectional"))
      (node (ref "R82") (pin "2") (pinfunction "2_2") (pintype "passive"))
      (node (ref "R84") (pin "1") (pinfunction "1_1") (pintype "passive"))
    )
    (net (code "110") (name "/U_meas_P12V0") (class "Default")
      (node (ref "C92") (pin "1") (pinfunction "1_1") (pintype "passive"))
      (node (ref "IC9") (pin "28") (pinfunction "PC2_C_28") (pintype "bidirectional"))
      (node (ref "R81") (pin "1") (pinfunction "1_1") (pintype "passive"))
      (node (ref "R83") (pin "1") (pinfunction "1_1") (pintype "passive"))
    )
    (net (code "111") (name "/Vref0") (class "Default")
      (node (ref "IC9") (pin "13") (pinfunction "PF3_13") (pintype "bidirectional"))
    )
    (net (code "112") (name "/Vref1") (class "Default")
      (node (ref "IC9") (pin "14") (pinfunction "PF4_14") (pintype "bidirectional"))
    )
    (net (code "113") (name "/Vref2") (class "Default")
      (node (ref "IC9") (pin "15") (pinfunction "PF5_15") (pintype "bidirectional"))
    )
    (net (code "114") (name "/Vref3") (class "Default")
      (node (ref "IC9") (pin "18") (pinfunction "PF6_18") (pintype "bidirectional"))
    )
    (net (code "116") (name "/~{SHDN}0") (class "Default")
      (node (ref "IC9") (pin "89") (pinfunction "PG4_89") (pintype "bidirectional"))
    )
    (net (code "117") (name "/~{SHDN}1") (class "Default")
      (node (ref "IC9") (pin "90") (pinfunction "PG5_90") (pintype "bidirectional"))
    )
    (net (code "118") (name "/~{SHDN}2") (class "Default")
      (node (ref "IC9") (pin "91") (pinfunction "PG6_91") (pintype "bidirectional"))
    )
    (net (code "119") (name "/~{SHDN}3") (class "Default")
      (node (ref "IC9") (pin "92") (pinfunction "PG7_92") (pintype "bidirectional"))
    )
    (net (code "121") (name "GND") (class "Default")
      (node (ref "C126") (pin "2") (pinfunction "2_2") (pintype "passive"))
      (node (ref "C17") (pin "1") (pinfunction "1_1") (pintype "passive"))
      (node (ref "C18") (pin "1") (pinfunction "1_1") (pintype "passive"))
      (node (ref "C21") (pin "2") (pinfunction "2_2") (pintype "passive"))
      (node (ref "C22") (pin "2") (pinfunction "2_2") (pintype "passive"))
      (node (ref "C23") (pin "1") (pinfunction "1_1") (pintype "passive"))
      (node (ref "C24") (pin "1") (pinfunction "1_1") (pintype "passive"))
      (node (ref "C25") (pin "1") (pinfunction "1_1") (pintype "passive"))
      (node (ref "C28") (pin "1") (pinfunction "1_1") (pintype "passive"))
      (node (ref "C29") (pin "1") (pinfunction "1_1") (pintype "passive"))
      (node (ref "C30") (pin "1") (pinfunction "1_1") (pintype "passive"))
      (node (ref "C31") (pin "1") (pinfunction "1_1") (pintype "passive"))
      (node (ref "C32") (pin "1") (pinfunction "1_1") (pintype "passive"))
      (node (ref "C33") (pin "1") (pinfunction "1_1") (pintype "passive"))
      (node (ref "C35") (pin "2") (pinfunction "2_2") (pintype "passive"))
      (node (ref "C64") (pin "1") (pinfunction "1_1") (pintype "passive"))
      (node (ref "C92") (pin "2") (pinfunction "2_2") (pintype "passive"))
      (node (ref "C93") (pin "2") (pinfunction "2_2") (pintype "passive"))
      (node (ref "C94") (pin "1") (pinfunction "1_1") (pintype "passive"))
      (node (ref "C95") (pin "1") (pinfunction "1_1") (pintype "passive"))
      (node (ref "C96") (pin "1") (pinfunction "1_1") (pintype "passive"))
      (node (ref "C97") (pin "1") (pinfunction "1_1") (pintype "passive"))
      (node (ref "C98") (pin "1") (pinfunction "1_1") (pintype "passive"))
      (node (ref "C99") (pin "2") (pinfunction "2_2") (pintype "passive"))
      (node (ref "D26") (pin "2") (pinfunction "GND_2") (pintype "power_in"))
      (node (ref "IC13") (pin "1") (pinfunction "Vss_1") (pintype "power_in"))
      (node (ref "IC9") (pin "107") (pinfunction "VSS_107") (pintype "power_in"))
      (node (ref "IC9") (pin "120") (pinfunction "VSS_120") (pintype "power_in"))
      (node (ref "IC9") (pin "130") (pinfunction "VSS_130") (pintype "power_in"))
      (node (ref "IC9") (pin "16") (pinfunction "VSS_16") (pintype "power_in"))
      (node (ref "IC9") (pin "31") (pinfunction "VSSA_31") (pintype "power_in"))
      (node (ref "IC9") (pin "38") (pinfunction "VSS_38") (pintype "power_in"))
      (node (ref "IC9") (pin "51") (pinfunction "VSS_51") (pintype "power_in"))
      (node (ref "IC9") (pin "61") (pinfunction "VSS_61") (pintype "power_in"))
      (node (ref "IC9") (pin "83") (pinfunction "VSS_83") (pintype "power_in"))
      (node (ref "IC9") (pin "94") (pinfunction "VSS_94") (pintype "power_in"))
      (node (ref "J21") (pin "3") (pinfunction "3_3") (pintype "bidirectional"))
      (node (ref "J21") (pin "5") (pinfunction "5_5") (pintype "bidirectional"))
      (node (ref "LD11") (pin "1") (pinfunction "C_1") (pintype "passive"))
      (node (ref "LD11") (pin "3") (pinfunction "C_3") (pintype "passive"))
      (node (ref "LD11") (pin "5") (pinfunction "C_5") (pintype "passive"))
      (node (ref "LD11") (pin "7") (pinfunction "C_7") (pintype "passive"))
      (node (ref "LD12") (pin "1") (pinfunction "C_1") (pintype "passive"))
      (node (ref "LD12") (pin "3") (pinfunction "C_3") (pintype "passive"))
      (node (ref "LD12") (pin "5") (pinfunction "C_5") (pintype "passive"))
      (node (ref "LD12") (pin "7") (pinfunction "C_7") (pintype "passive"))
      (node (ref "R106") (pin "2") (pinfunction "2_2") (pintype "passive"))
      (node (ref "R119") (pin "2") (pinfunction "2_2") (pintype "passive"))
      (node (ref "R32") (pin "1") (pinfunction "1_1") (pintype "passive"))
      (node (ref "R63") (pin "2") (pinfunction "2_2") (pintype "passive"))
      (node (ref "R8") (pin "2") (pinfunction "2_2") (pintype "passive"))
      (node (ref "R81") (pin "2") (pinfunction "2_2") (pintype "passive"))
      (node (ref "R84") (pin "2") (pinfunction "2_2") (pintype "passive"))
      (node (ref "R93") (pin "2") (pinfunction "2_2") (pintype "passive"))
      (node (ref "W1") (pin "4") (pinfunction "4_4") (pintype "bidirectional"))
      (node (ref "W2") (pin "5") (pinfunction "5_5") (pintype "bidirectional"))
    )
    (net (code "122") (name "Net-(C17-Pad2)") (class "Default")
      (node (ref "C17") (pin "2") (pinfunction "2_2") (pintype "passive"))
      (node (ref "IC9") (pin "106") (pinfunction "VCAP_106") (pintype "power_in"))
    )
    (net (code "123") (name "Net-(C18-Pad2)") (class "Default")
      (node (ref "C18") (pin "2") (pinfunction "2_2") (pintype "passive"))
      (node (ref "IC9") (pin "71") (pinfunction "VCAP_71") (pintype "power_in"))
    )
    (net (code "124") (name "Net-(IC9A-VBAT)") (class "Default")
      (node (ref "C64") (pin "2") (pinfunction "2_2") (pintype "passive"))
      (node (ref "IC9") (pin "6") (pinfunction "VBAT_6") (pintype "power_in"))
    )
    (net (code "125") (name "Net-(IC9A-VDDA)") (class "Default")
      (node (ref "C23") (pin "2") (pinfunction "2_2") (pintype "passive"))
      (node (ref "C28") (pin "2") (pinfunction "2_2") (pintype "passive"))
      (node (ref "IC9") (pin "33") (pinfunction "VDDA_33") (pintype "power_in"))
      (node (ref "L5") (pin "1") (pinfunction "1_1") (pintype "passive"))
    )
    (net (code "126") (name "Net-(IC9A-VREF+)") (class "Default")
      (node (ref "C24") (pin "2") (pinfunction "2_2") (pintype "passive"))
      (node (ref "C25") (pin "2") (pinfunction "2_2") (pintype "passive"))
      (node (ref "IC9") (pin "32") (pinfunction "VREF+_32") (pintype "power_in"))
      (node (ref "R70") (pin "1") (pinfunction "1_1") (pintype "passive"))
    )
    (net (code "127") (name "Net-(IC9B-PB2)") (class "Default")
      (node (ref "IC9") (pin "48") (pinfunction "PB2_48") (pintype "bidirectional"))
      (node (ref "R32") (pin "2") (pinfunction "2_2") (pintype "passive"))
    )
    (net (code "128") (name "Net-(IC9C-BOOT0)") (class "Default")
      (node (ref "IC9") (pin "138") (pinfunction "BOOT0_138") (pintype "output"))
      (node (ref "JP2") (pin "2") (pinfunction "E2_2") (pintype "passive"))
      (node (ref "R63") (pin "1") (pinfunction "1_1") (pintype "passive"))
    )
    (net (code "129") (name "Net-(IC9C-PA9)") (class "Default")
      (node (ref "IC9") (pin "101") (pinfunction "PA9_101") (pintype "bidirectional"))
      (node (ref "R34") (pin "1") (pinfunction "1_1") (pintype "passive"))
    )
    (net (code "130") (name "Net-(IC9C-PH0-OSC_IN)") (class "Default")
      (node (ref "C21") (pin "1") (pinfunction "1_1") (pintype "passive"))
      (node (ref "IC9") (pin "23") (pinfunction "PH0-OSC_IN_23") (pintype "bidirectional"))
      (node (ref "Q1") (pin "1") (pinfunction "OSC1_1") (pintype "passive"))
    )
    (net (code "131") (name "Net-(IC9C-PH1-OSC_OUT)") (class "Default")
      (node (ref "C22") (pin "1") (pinfunction "1_1") (pintype "passive"))
      (node (ref "IC9") (pin "24") (pinfunction "PH1-OSC_OUT_24") (pintype "bidirectional"))
      (node (ref "Q1") (pin "2") (pinfunction "OSC2_2") (pintype "passive"))
    )
    (net (code "132") (name "Net-(LD11A-A)") (class "Default")
      (node (ref "LD11") (pin "2") (pinfunction "A_2") (pintype "passive"))
      (node (ref "R143") (pin "2") (pinfunction "2_2") (pintype "passive"))
    )
    (net (code "133") (name "Net-(LD11B-A)") (class "Default")
      (node (ref "LD11") (pin "4") (pinfunction "A_4") (pintype "passive"))
      (node (ref "R144") (pin "2") (pinfunction "2_2") (pintype "passive"))
    )
    (net (code "134") (name "Net-(LD11C-A)") (class "Default")
      (node (ref "LD11") (pin "6") (pinfunction "A_6") (pintype "passive"))
      (node (ref "R145") (pin "2") (pinfunction "2_2") (pintype "passive"))
    )
    (net (code "135") (name "Net-(LD11D-A)") (class "Default")
      (node (ref "LD11") (pin "8") (pinfunction "A_8") (pintype "passive"))
      (node (ref "R146") (pin "2") (pinfunction "2_2") (pintype "passive"))
    )
    (net (code "136") (name "Net-(LD12A-A)") (class "Default")
      (node (ref "LD12") (pin "2") (pinfunction "A_2") (pintype "passive"))
      (node (ref "R147") (pin "2") (pinfunction "2_2") (pintype "passive"))
    )
    (net (code "137") (name "Net-(LD12B-A)") (class "Default")
      (node (ref "LD12") (pin "4") (pinfunction "A_4") (pintype "passive"))
      (node (ref "R148") (pin "2") (pinfunction "2_2") (pintype "passive"))
    )
    (net (code "138") (name "Net-(LD12C-A)") (class "Default")
      (node (ref "LD12") (pin "6") (pinfunction "A_6") (pintype "passive"))
      (node (ref "R149") (pin "2") (pinfunction "2_2") (pintype "passive"))
    )
    (net (code "139") (name "Net-(LD12D-A)") (class "Default")
      (node (ref "LD12") (pin "8") (pinfunction "A_8") (pintype "passive"))
      (node (ref "R150") (pin "2") (pinfunction "2_2") (pintype "passive"))
    )
    (net (code "140") (name "P3V0REF") (class "Default")
      (node (ref "R70") (pin "2") (pinfunction "2_2") (pintype "passive"))
    )
    (net (code "141") (name "P3V3") (class "Default")
      (node (ref "C29") (pin "2") (pinfunction "2_2") (pintype "passive"))
      (node (ref "C30") (pin "2") (pinfunction "2_2") (pintype "passive"))
      (node (ref "C31") (pin "2") (pinfunction "2_2") (pintype "passive"))
      (node (ref "C32") (pin "2") (pinfunction "2_2") (pintype "passive"))
      (node (ref "C33") (pin "2") (pinfunction "2_2") (pintype "passive"))
      (node (ref "C35") (pin "1") (pinfunction "1_1") (pintype "passive"))
      (node (ref "C94") (pin "2") (pinfunction "2_2") (pintype "passive"))
      (node (ref "C95") (pin "2") (pinfunction "2_2") (pintype "passive"))
      (node (ref "C96") (pin "2") (pinfunction "2_2") (pintype "passive"))
      (node (ref "C97") (pin "2") (pinfunction "2_2") (pintype "passive"))
      (node (ref "C98") (pin "2") (pinfunction "2_2") (pintype "passive"))
      (node (ref "C99") (pin "1") (pinfunction "1_1") (pintype "passive"))
      (node (ref "D26") (pin "5") (pinfunction "VBUS_5") (pintype "power_in"))
      (node (ref "IC13") (pin "3") (pinfunction "Vcc_3") (pintype "power_in"))
      (node (ref "IC9") (pin "108") (pinfunction "VDD_108") (pintype "power_in"))
      (node (ref "IC9") (pin "121") (pinfunction "VDD_121") (pintype "power_in"))
      (node (ref "IC9") (pin "131") (pinfunction "VDD_131") (pintype "power_in"))
      (node (ref "IC9") (pin "143") (pinfunction "PDR_ON_143") (pintype "power_in"))
      (node (ref "IC9") (pin "144") (pinfunction "VDD_144") (pintype "power_in"))
      (node (ref "IC9") (pin "17") (pinfunction "VDD_17") (pintype "power_in"))
      (node (ref "IC9") (pin "30") (pinfunction "VDD_30") (pintype "power_in"))
      (node (ref "IC9") (pin "39") (pinfunction "VDD_39") (pintype "power_in"))
      (node (ref "IC9") (pin "52") (pinfunction "VDD_52") (pintype "power_in"))
      (node (ref "IC9") (pin "62") (pinfunction "VDD_62") (pintype "power_in"))
      (node (ref "IC9") (pin "72") (pinfunction "VDD_72") (pintype "power_in"))
      (node (ref "IC9") (pin "84") (pinfunction "VDD_84") (pintype "power_in"))
      (node (ref "IC9") (pin "95") (pinfunction "VDD33USB_95") (pintype "power_in"))
      (node (ref "J21") (pin "1") (pinfunction "1_1") (pintype "bidirectional"))
      (node (ref "JP2") (pin "1") (pinfunction "E1_1") (pintype "passive"))
      (node (ref "L5") (pin "2") (pinfunction "2_2") (pintype "passive"))
      (node (ref "R33") (pin "2") (pinfunction "2_2") (pintype "passive"))
      (node (ref "R53") (pin "2") (pinfunction "2_2") (pintype "passive"))
      (node (ref "R61") (pin "2") (pinfunction "2_2") (pintype "passive"))
      (node (ref "R62") (pin "1") (pinfunction "1_1") (pintype "passive"))
      (node (ref "R7") (pin "2") (pinfunction "2_2") (pintype "passive"))
      (node (ref "R92") (pin "2") (pinfunction "2_2") (pintype "passive"))
      (node (ref "W1") (pin "1") (pinfunction "1_1") (pintype "bidirectional"))
      (node (ref "W2") (pin "10") (pinfunction "10_10") (pintype "bidirectional"))
    )
    (net (code "142") (name "P5V0") (class "Default")
      (node (ref "R82") (pin "1") (pinfunction "1_1") (pintype "passive"))
    )
    (net (code "143") (name "P12V0") (class "Default")
      (node (ref "R83") (pin "2") (pinfunction "2_2") (pintype "passive"))
    )
    (net (code "144") (name "unconnected-(IC9C-PD1-Pad115)") (class "Default")
      (node (ref "IC9") (pin "115") (pinfunction "PD1_115") (pintype "bidirectional"))
    )
    (net (code "145") (name "unconnected-(IC9C-PF11-Pad49)") (class "Default")
      (node (ref "IC9") (pin "49") (pinfunction "PF11_49") (pintype "bidirectional"))
    )
    (net (code "146") (name "unconnected-(J21-Pad7)") (class "Default")
      (node (ref "J21") (pin "7") (pinfunction "7_7") (pintype "bidirectional"))
    )
    (net (code "147") (name "unconnected-(J21-Pad9)") (class "Default")
      (node (ref "J21") (pin "9") (pinfunction "9_9") (pintype "bidirectional"))
    )
  )
)
